# A78_Maxi2.net
KiCad netlist of a schematic drawn in EAGLE
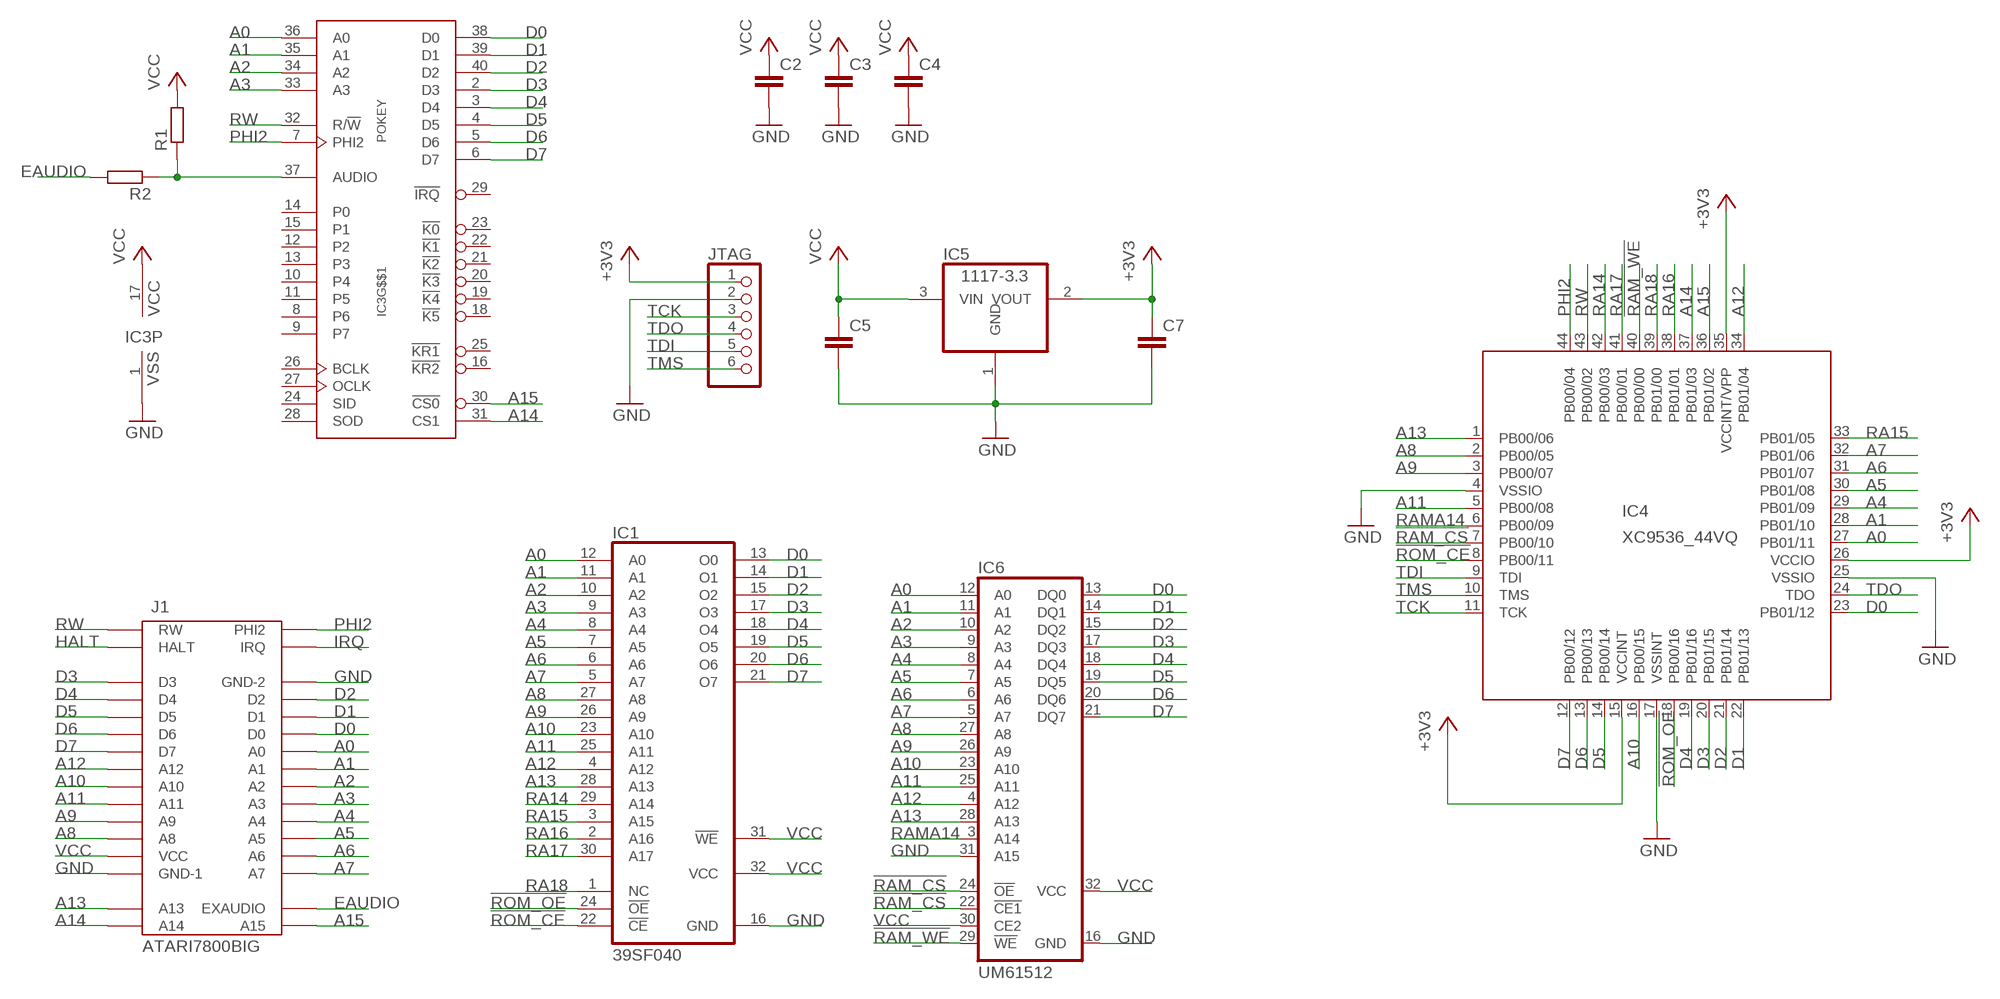
[diagram p0: schematic, sheet 1]

(export (version "E")
  (design (tool "Eeschema 10.0.6"))
  (components
    (comp (ref "C2")
      (value "C-EU025-025X050")
      (footprint "eagle-import:C025-025X050")
      (libsource (lib "eagle-import") (part "C-EU025-025X050"))
    )
    (comp (ref "C3")
      (value "C-EUC0805")
      (footprint "eagle-import:C0805")
      (libsource (lib "eagle-import") (part "C-EUC0805"))
    )
    (comp (ref "C4")
      (value "C-EUC0805")
      (footprint "eagle-import:C0805")
      (libsource (lib "eagle-import") (part "C-EUC0805"))
    )
    (comp (ref "C5")
      (value "C-EUC0805")
      (footprint "eagle-import:C0805")
      (libsource (lib "eagle-import") (part "C-EUC0805"))
    )
    (comp (ref "C7")
      (value "C-EUC0805")
      (footprint "eagle-import:C0805")
      (libsource (lib "eagle-import") (part "C-EUC0805"))
    )
    (comp (ref "IC1")
      (value "39SF040")
      (footprint "eagle-import:DIL32")
      (libsource (lib "eagle-import") (part "39SF020"))
    )
    (comp (ref "IC3")
      (value "POKEY")
      (footprint "eagle-import:DIL40")
      (libsource (lib "eagle-import") (part "POKEY"))
    )
    (comp (ref "IC4")
      (value "XC9536_44VQ")
      (footprint "eagle-import:SQFP-S-10X10-44")
      (fields (field (name "MPN") "XC9536-15VQG44C"))
      (libsource (lib "eagle-import") (part "XC9536_44VQ"))
    )
    (comp (ref "IC5")
      (value "1117-3.3")
      (footprint "eagle-import:SOT223")
      (fields (field (name "MPN") "REG1117"))
      (libsource (lib "eagle-import") (part "REG1117"))
    )
    (comp (ref "IC6")
      (value "UM61512")
      (footprint "eagle-import:DIL32-NARROW")
      (libsource (lib "eagle-import") (part "UM61512"))
    )
    (comp (ref "J1")
      (value "ATARI7800BIG")
      (footprint "eagle-import:ATARI-7800-BIG")
      (libsource (lib "eagle-import") (part "ATARI7800BIG"))
    )
    (comp (ref "JTAG")
      (value "PINHD-1X6")
      (footprint "eagle-import:1X06")
      (libsource (lib "eagle-import") (part "PINHD-1X6"))
    )
    (comp (ref "R1")
      (value "R-EU_R0805")
      (footprint "eagle-import:R0805")
      (libsource (lib "eagle-import") (part "R-EU_R0805"))
    )
    (comp (ref "R2")
      (value "R-EU_R0805")
      (footprint "eagle-import:R0805")
      (libsource (lib "eagle-import") (part "R-EU_R0805"))
    )
  )
  (nets
    (net (code "1") (name "+3V3") (class "Default")
      (node (ref "C7") (pin "1") (pinfunction "1_1") (pintype "passive"))
      (node (ref "IC4") (pin "15") (pinfunction "VCCINT_15") (pintype "power_in"))
      (node (ref "IC4") (pin "26") (pinfunction "VCCIO_26") (pintype "power_in"))
      (node (ref "IC4") (pin "35") (pinfunction "VCCINT/VPP_35") (pintype "input"))
      (node (ref "IC5") (pin "2") (pinfunction "VOUT_2") (pintype "output"))
      (node (ref "JTAG") (pin "1") (pinfunction "1_1") (pintype "passive"))
    )
    (net (code "2") (name "/A0") (class "Default")
      (node (ref "IC1") (pin "12") (pinfunction "A0_12") (pintype "input"))
      (node (ref "IC3") (pin "36") (pinfunction "A0_36") (pintype "input"))
      (node (ref "IC4") (pin "27") (pinfunction "PB01/11_27") (pintype "bidirectional"))
      (node (ref "IC6") (pin "12") (pinfunction "A0_12") (pintype "input"))
      (node (ref "J1") (pin "26") (pinfunction "A0_26") (pintype "passive"))
    )
    (net (code "3") (name "/A1") (class "Default")
      (node (ref "IC1") (pin "11") (pinfunction "A1_11") (pintype "input"))
      (node (ref "IC3") (pin "35") (pinfunction "A1_35") (pintype "input"))
      (node (ref "IC4") (pin "28") (pinfunction "PB01/10_28") (pintype "bidirectional"))
      (node (ref "IC6") (pin "11") (pinfunction "A1_11") (pintype "input"))
      (node (ref "J1") (pin "25") (pinfunction "A1_25") (pintype "passive"))
    )
    (net (code "4") (name "/A2") (class "Default")
      (node (ref "IC1") (pin "10") (pinfunction "A2_10") (pintype "input"))
      (node (ref "IC3") (pin "34") (pinfunction "A2_34") (pintype "input"))
      (node (ref "IC6") (pin "10") (pinfunction "A2_10") (pintype "input"))
      (node (ref "J1") (pin "24") (pinfunction "A2_24") (pintype "passive"))
    )
    (net (code "5") (name "/A3") (class "Default")
      (node (ref "IC1") (pin "9") (pinfunction "A3_9") (pintype "input"))
      (node (ref "IC3") (pin "33") (pinfunction "A3_33") (pintype "input"))
      (node (ref "IC6") (pin "9") (pinfunction "A3_9") (pintype "input"))
      (node (ref "J1") (pin "23") (pinfunction "A3_23") (pintype "passive"))
    )
    (net (code "6") (name "/A4") (class "Default")
      (node (ref "IC1") (pin "8") (pinfunction "A4_8") (pintype "input"))
      (node (ref "IC4") (pin "29") (pinfunction "PB01/09_29") (pintype "bidirectional"))
      (node (ref "IC6") (pin "8") (pinfunction "A4_8") (pintype "input"))
      (node (ref "J1") (pin "22") (pinfunction "A4_22") (pintype "passive"))
    )
    (net (code "7") (name "/A5") (class "Default")
      (node (ref "IC1") (pin "7") (pinfunction "A5_7") (pintype "input"))
      (node (ref "IC4") (pin "30") (pinfunction "PB01/08_30") (pintype "bidirectional"))
      (node (ref "IC6") (pin "7") (pinfunction "A5_7") (pintype "input"))
      (node (ref "J1") (pin "21") (pinfunction "A5_21") (pintype "passive"))
    )
    (net (code "8") (name "/A6") (class "Default")
      (node (ref "IC1") (pin "6") (pinfunction "A6_6") (pintype "input"))
      (node (ref "IC4") (pin "31") (pinfunction "PB01/07_31") (pintype "bidirectional"))
      (node (ref "IC6") (pin "6") (pinfunction "A6_6") (pintype "input"))
      (node (ref "J1") (pin "20") (pinfunction "A6_20") (pintype "passive"))
    )
    (net (code "9") (name "/A7") (class "Default")
      (node (ref "IC1") (pin "5") (pinfunction "A7_5") (pintype "input"))
      (node (ref "IC4") (pin "32") (pinfunction "PB01/06_32") (pintype "bidirectional"))
      (node (ref "IC6") (pin "5") (pinfunction "A7_5") (pintype "input"))
      (node (ref "J1") (pin "19") (pinfunction "A7_19") (pintype "passive"))
    )
    (net (code "10") (name "/A8") (class "Default")
      (node (ref "IC1") (pin "27") (pinfunction "A8_27") (pintype "input"))
      (node (ref "IC4") (pin "2") (pinfunction "PB00/05_2") (pintype "bidirectional"))
      (node (ref "IC6") (pin "27") (pinfunction "A8_27") (pintype "input"))
      (node (ref "J1") (pin "12") (pinfunction "A8_12") (pintype "passive"))
    )
    (net (code "11") (name "/A9") (class "Default")
      (node (ref "IC1") (pin "26") (pinfunction "A9_26") (pintype "input"))
      (node (ref "IC4") (pin "3") (pinfunction "PB00/07_3") (pintype "bidirectional"))
      (node (ref "IC6") (pin "26") (pinfunction "A9_26") (pintype "input"))
      (node (ref "J1") (pin "11") (pinfunction "A9_11") (pintype "passive"))
    )
    (net (code "12") (name "/A10") (class "Default")
      (node (ref "IC1") (pin "23") (pinfunction "A10_23") (pintype "input"))
      (node (ref "IC4") (pin "16") (pinfunction "PB00/15_16") (pintype "bidirectional"))
      (node (ref "IC6") (pin "23") (pinfunction "A10_23") (pintype "input"))
      (node (ref "J1") (pin "9") (pinfunction "A10_9") (pintype "passive"))
    )
    (net (code "13") (name "/A11") (class "Default")
      (node (ref "IC1") (pin "25") (pinfunction "A11_25") (pintype "input"))
      (node (ref "IC4") (pin "5") (pinfunction "PB00/08_5") (pintype "bidirectional"))
      (node (ref "IC6") (pin "25") (pinfunction "A11_25") (pintype "input"))
      (node (ref "J1") (pin "10") (pinfunction "A11_10") (pintype "passive"))
    )
    (net (code "14") (name "/A12") (class "Default")
      (node (ref "IC1") (pin "4") (pinfunction "A12_4") (pintype "input"))
      (node (ref "IC4") (pin "34") (pinfunction "PB01/04_34") (pintype "bidirectional"))
      (node (ref "IC6") (pin "4") (pinfunction "A12_4") (pintype "input"))
      (node (ref "J1") (pin "8") (pinfunction "A12_8") (pintype "passive"))
    )
    (net (code "15") (name "/A13") (class "Default")
      (node (ref "IC1") (pin "28") (pinfunction "A13_28") (pintype "input"))
      (node (ref "IC4") (pin "1") (pinfunction "PB00/06_1") (pintype "bidirectional"))
      (node (ref "IC6") (pin "28") (pinfunction "A13_28") (pintype "input"))
      (node (ref "J1") (pin "15") (pinfunction "A13_15") (pintype "passive"))
    )
    (net (code "16") (name "/A14") (class "Default")
      (node (ref "IC3") (pin "31") (pinfunction "CS1_31") (pintype "input"))
      (node (ref "IC4") (pin "37") (pinfunction "PB01/03_37") (pintype "bidirectional"))
      (node (ref "J1") (pin "16") (pinfunction "A14_16") (pintype "passive"))
    )
    (net (code "17") (name "/A15") (class "Default")
      (node (ref "IC3") (pin "30") (pinfunction "~{CS0}_30") (pintype "input"))
      (node (ref "IC4") (pin "36") (pinfunction "PB01/02_36") (pintype "bidirectional"))
      (node (ref "J1") (pin "17") (pinfunction "A15_17") (pintype "passive"))
    )
    (net (code "18") (name "/D0") (class "Default")
      (node (ref "IC1") (pin "13") (pinfunction "O0_13") (pintype "tri_state"))
      (node (ref "IC3") (pin "38") (pinfunction "D0_38") (pintype "output"))
      (node (ref "IC4") (pin "23") (pinfunction "PB01/12_23") (pintype "bidirectional"))
      (node (ref "IC6") (pin "13") (pinfunction "DQ0_13") (pintype "bidirectional"))
      (node (ref "J1") (pin "27") (pinfunction "D0_27") (pintype "passive"))
    )
    (net (code "19") (name "/D1") (class "Default")
      (node (ref "IC1") (pin "14") (pinfunction "O1_14") (pintype "tri_state"))
      (node (ref "IC3") (pin "39") (pinfunction "D1_39") (pintype "output"))
      (node (ref "IC4") (pin "22") (pinfunction "PB01/13_22") (pintype "bidirectional"))
      (node (ref "IC6") (pin "14") (pinfunction "DQ1_14") (pintype "bidirectional"))
      (node (ref "J1") (pin "28") (pinfunction "D1_28") (pintype "passive"))
    )
    (net (code "20") (name "/D2") (class "Default")
      (node (ref "IC1") (pin "15") (pinfunction "O2_15") (pintype "tri_state"))
      (node (ref "IC3") (pin "40") (pinfunction "D2_40") (pintype "output"))
      (node (ref "IC4") (pin "21") (pinfunction "PB01/14_21") (pintype "bidirectional"))
      (node (ref "IC6") (pin "15") (pinfunction "DQ2_15") (pintype "bidirectional"))
      (node (ref "J1") (pin "29") (pinfunction "D2_29") (pintype "passive"))
    )
    (net (code "21") (name "/D3") (class "Default")
      (node (ref "IC1") (pin "17") (pinfunction "O3_17") (pintype "tri_state"))
      (node (ref "IC3") (pin "2") (pinfunction "D3_2") (pintype "output"))
      (node (ref "IC4") (pin "20") (pinfunction "PB01/15_20") (pintype "bidirectional"))
      (node (ref "IC6") (pin "17") (pinfunction "DQ3_17") (pintype "bidirectional"))
      (node (ref "J1") (pin "3") (pinfunction "D3_3") (pintype "passive"))
    )
    (net (code "22") (name "/D4") (class "Default")
      (node (ref "IC1") (pin "18") (pinfunction "O4_18") (pintype "tri_state"))
      (node (ref "IC3") (pin "3") (pinfunction "D4_3") (pintype "output"))
      (node (ref "IC4") (pin "19") (pinfunction "PB01/16_19") (pintype "bidirectional"))
      (node (ref "IC6") (pin "18") (pinfunction "DQ4_18") (pintype "bidirectional"))
      (node (ref "J1") (pin "4") (pinfunction "D4_4") (pintype "passive"))
    )
    (net (code "23") (name "/D5") (class "Default")
      (node (ref "IC1") (pin "19") (pinfunction "O5_19") (pintype "tri_state"))
      (node (ref "IC3") (pin "4") (pinfunction "D5_4") (pintype "output"))
      (node (ref "IC4") (pin "14") (pinfunction "PB00/14_14") (pintype "bidirectional"))
      (node (ref "IC6") (pin "19") (pinfunction "DQ5_19") (pintype "bidirectional"))
      (node (ref "J1") (pin "5") (pinfunction "D5_5") (pintype "passive"))
    )
    (net (code "24") (name "/D6") (class "Default")
      (node (ref "IC1") (pin "20") (pinfunction "O6_20") (pintype "tri_state"))
      (node (ref "IC3") (pin "5") (pinfunction "D6_5") (pintype "output"))
      (node (ref "IC4") (pin "13") (pinfunction "PB00/13_13") (pintype "bidirectional"))
      (node (ref "IC6") (pin "20") (pinfunction "DQ6_20") (pintype "bidirectional"))
      (node (ref "J1") (pin "6") (pinfunction "D6_6") (pintype "passive"))
    )
    (net (code "25") (name "/D7") (class "Default")
      (node (ref "IC1") (pin "21") (pinfunction "O7_21") (pintype "tri_state"))
      (node (ref "IC3") (pin "6") (pinfunction "D7_6") (pintype "output"))
      (node (ref "IC4") (pin "12") (pinfunction "PB00/12_12") (pintype "bidirectional"))
      (node (ref "IC6") (pin "21") (pinfunction "DQ7_21") (pintype "bidirectional"))
      (node (ref "J1") (pin "7") (pinfunction "D7_7") (pintype "passive"))
    )
    (net (code "26") (name "/EAUDIO") (class "Default")
      (node (ref "J1") (pin "18") (pinfunction "EXAUDIO_18") (pintype "passive"))
      (node (ref "R2") (pin "2") (pinfunction "2_2") (pintype "passive"))
    )
    (net (code "27") (name "/HALT") (class "Default")
      (node (ref "J1") (pin "2") (pinfunction "HALT_2") (pintype "passive"))
    )
    (net (code "28") (name "/IRQ") (class "Default")
      (node (ref "J1") (pin "31") (pinfunction "IRQ_31") (pintype "passive"))
    )
    (net (code "29") (name "/PHI2") (class "Default")
      (node (ref "IC3") (pin "7") (pinfunction "PHI2_7") (pintype "input"))
      (node (ref "IC4") (pin "44") (pinfunction "PB00/04_44") (pintype "bidirectional"))
      (node (ref "J1") (pin "32") (pinfunction "PHI2_32") (pintype "passive"))
    )
    (net (code "30") (name "/RA14") (class "Default")
      (node (ref "IC1") (pin "29") (pinfunction "A14_29") (pintype "input"))
      (node (ref "IC4") (pin "42") (pinfunction "PB00/03_42") (pintype "bidirectional"))
    )
    (net (code "31") (name "/RA15") (class "Default")
      (node (ref "IC1") (pin "3") (pinfunction "A15_3") (pintype "input"))
      (node (ref "IC4") (pin "33") (pinfunction "PB01/05_33") (pintype "bidirectional"))
    )
    (net (code "32") (name "/RA16") (class "Default")
      (node (ref "IC1") (pin "2") (pinfunction "A16_2") (pintype "input"))
      (node (ref "IC4") (pin "38") (pinfunction "PB01/01_38") (pintype "bidirectional"))
    )
    (net (code "33") (name "/RA17") (class "Default")
      (node (ref "IC1") (pin "30") (pinfunction "A17_30") (pintype "input"))
      (node (ref "IC4") (pin "41") (pinfunction "PB00/01_41") (pintype "bidirectional"))
    )
    (net (code "34") (name "/RA18") (class "Default")
      (node (ref "IC1") (pin "1") (pinfunction "NC_1") (pintype "input"))
      (node (ref "IC4") (pin "39") (pinfunction "PB01/00_39") (pintype "bidirectional"))
    )
    (net (code "35") (name "/RAMA14") (class "Default")
      (node (ref "IC4") (pin "6") (pinfunction "PB00/09_6") (pintype "bidirectional"))
      (node (ref "IC6") (pin "3") (pinfunction "A14_3") (pintype "input"))
    )
    (net (code "36") (name "/RW") (class "Default")
      (node (ref "IC3") (pin "32") (pinfunction "R/~{W}_32") (pintype "input"))
      (node (ref "IC4") (pin "43") (pinfunction "PB00/02_43") (pintype "bidirectional"))
      (node (ref "J1") (pin "1") (pinfunction "RW_1") (pintype "passive"))
    )
    (net (code "37") (name "/TCK") (class "Default")
      (node (ref "IC4") (pin "11") (pinfunction "TCK_11") (pintype "input"))
      (node (ref "JTAG") (pin "3") (pinfunction "3_3") (pintype "passive"))
    )
    (net (code "38") (name "/TDI") (class "Default")
      (node (ref "IC4") (pin "9") (pinfunction "TDI_9") (pintype "input"))
      (node (ref "JTAG") (pin "5") (pinfunction "5_5") (pintype "passive"))
    )
    (net (code "39") (name "/TDO") (class "Default")
      (node (ref "IC4") (pin "24") (pinfunction "TDO_24") (pintype "output"))
      (node (ref "JTAG") (pin "4") (pinfunction "4_4") (pintype "passive"))
    )
    (net (code "40") (name "/TMS") (class "Default")
      (node (ref "IC4") (pin "10") (pinfunction "TMS_10") (pintype "input"))
      (node (ref "JTAG") (pin "6") (pinfunction "6_6") (pintype "passive"))
    )
    (net (code "41") (name "/~{RAM_CS}") (class "Default")
      (node (ref "IC4") (pin "7") (pinfunction "PB00/10_7") (pintype "bidirectional"))
      (node (ref "IC6") (pin "22") (pinfunction "~{CE1}_22") (pintype "input"))
      (node (ref "IC6") (pin "24") (pinfunction "~{OE}_24") (pintype "input"))
    )
    (net (code "42") (name "/~{RAM_WE}") (class "Default")
      (node (ref "IC4") (pin "40") (pinfunction "PB00/00_40") (pintype "bidirectional"))
      (node (ref "IC6") (pin "29") (pinfunction "~{WE}_29") (pintype "input"))
    )
    (net (code "43") (name "/~{ROM_CE}") (class "Default")
      (node (ref "IC1") (pin "22") (pinfunction "~{CE}_22") (pintype "input"))
      (node (ref "IC4") (pin "8") (pinfunction "PB00/11_8") (pintype "bidirectional"))
    )
    (net (code "44") (name "/~{ROM_OE}") (class "Default")
      (node (ref "IC1") (pin "24") (pinfunction "~{OE}_24") (pintype "input"))
      (node (ref "IC4") (pin "18") (pinfunction "PB00/16_18") (pintype "bidirectional"))
    )
    (net (code "45") (name "GND") (class "Default")
      (node (ref "C2") (pin "2") (pinfunction "2_2") (pintype "passive"))
      (node (ref "C3") (pin "2") (pinfunction "2_2") (pintype "passive"))
      (node (ref "C4") (pin "2") (pinfunction "2_2") (pintype "passive"))
      (node (ref "C5") (pin "2") (pinfunction "2_2") (pintype "passive"))
      (node (ref "C7") (pin "2") (pinfunction "2_2") (pintype "passive"))
      (node (ref "IC1") (pin "16") (pinfunction "GND_16") (pintype "power_in"))
      (node (ref "IC3") (pin "1") (pinfunction "VSS_1") (pintype "power_in"))
      (node (ref "IC4") (pin "17") (pinfunction "VSSINT_17") (pintype "power_in"))
      (node (ref "IC4") (pin "25") (pinfunction "VSSIO_25") (pintype "power_in"))
      (node (ref "IC4") (pin "4") (pinfunction "VSSIO_4") (pintype "power_in"))
      (node (ref "IC5") (pin "1") (pinfunction "GND_1") (pintype "power_in"))
      (node (ref "IC6") (pin "16") (pinfunction "GND_16") (pintype "power_in"))
      (node (ref "IC6") (pin "31") (pinfunction "A15_31") (pintype "input"))
      (node (ref "J1") (pin "14") (pinfunction "GND-1_14") (pintype "passive"))
      (node (ref "J1") (pin "30") (pinfunction "GND-2_30") (pintype "passive"))
      (node (ref "JTAG") (pin "2") (pinfunction "2_2") (pintype "passive"))
    )
    (net (code "46") (name "Net-(IC3A-AUDIO)") (class "Default")
      (node (ref "IC3") (pin "37") (pinfunction "AUDIO_37") (pintype "output"))
      (node (ref "R1") (pin "1") (pinfunction "1_1") (pintype "passive"))
      (node (ref "R2") (pin "1") (pinfunction "1_1") (pintype "passive"))
    )
    (net (code "47") (name "VCC") (class "Default")
      (node (ref "C2") (pin "1") (pinfunction "1_1") (pintype "passive"))
      (node (ref "C3") (pin "1") (pinfunction "1_1") (pintype "passive"))
      (node (ref "C4") (pin "1") (pinfunction "1_1") (pintype "passive"))
      (node (ref "C5") (pin "1") (pinfunction "1_1") (pintype "passive"))
      (node (ref "IC1") (pin "31") (pinfunction "~{WE}_31") (pintype "passive"))
      (node (ref "IC1") (pin "32") (pinfunction "VCC_32") (pintype "power_in"))
      (node (ref "IC3") (pin "17") (pinfunction "VCC_17") (pintype "power_in"))
      (node (ref "IC5") (pin "3") (pinfunction "VIN_3") (pintype "input"))
      (node (ref "IC6") (pin "30") (pinfunction "CE2_30") (pintype "input"))
      (node (ref "IC6") (pin "32") (pinfunction "VCC_32") (pintype "power_in"))
      (node (ref "J1") (pin "13") (pinfunction "VCC_13") (pintype "passive"))
      (node (ref "R1") (pin "2") (pinfunction "2_2") (pintype "passive"))
    )
    (net (code "48") (name "unconnected-(IC3A-BCLK-Pad26)") (class "Default")
      (node (ref "IC3") (pin "26") (pinfunction "BCLK_26") (pintype "bidirectional"))
    )
    (net (code "49") (name "unconnected-(IC3A-OCLK-Pad27)") (class "Default")
      (node (ref "IC3") (pin "27") (pinfunction "OCLK_27") (pintype "output"))
    )
    (net (code "50") (name "unconnected-(IC3A-P0-Pad14)") (class "Default")
      (node (ref "IC3") (pin "14") (pinfunction "P0_14") (pintype "input"))
    )
    (net (code "51") (name "unconnected-(IC3A-P1-Pad15)") (class "Default")
      (node (ref "IC3") (pin "15") (pinfunction "P1_15") (pintype "input"))
    )
    (net (code "52") (name "unconnected-(IC3A-P2-Pad12)") (class "Default")
      (node (ref "IC3") (pin "12") (pinfunction "P2_12") (pintype "input"))
    )
    (net (code "53") (name "unconnected-(IC3A-P3-Pad13)") (class "Default")
      (node (ref "IC3") (pin "13") (pinfunction "P3_13") (pintype "input"))
    )
    (net (code "54") (name "unconnected-(IC3A-P4-Pad10)") (class "Default")
      (node (ref "IC3") (pin "10") (pinfunction "P4_10") (pintype "input"))
    )
    (net (code "55") (name "unconnected-(IC3A-P5-Pad11)") (class "Default")
      (node (ref "IC3") (pin "11") (pinfunction "P5_11") (pintype "input"))
    )
    (net (code "56") (name "unconnected-(IC3A-P6-Pad8)") (class "Default")
      (node (ref "IC3") (pin "8") (pinfunction "P6_8") (pintype "input"))
    )
    (net (code "57") (name "unconnected-(IC3A-P7-Pad9)") (class "Default")
      (node (ref "IC3") (pin "9") (pinfunction "P7_9") (pintype "input"))
    )
    (net (code "58") (name "unconnected-(IC3A-SID-Pad24)") (class "Default")
      (node (ref "IC3") (pin "24") (pinfunction "SID_24") (pintype "input"))
    )
    (net (code "59") (name "unconnected-(IC3A-SOD-Pad28)") (class "Default")
      (node (ref "IC3") (pin "28") (pinfunction "SOD_28") (pintype "output"))
    )
    (net (code "60") (name "unconnected-(IC3A-~{IRQ}-Pad29)") (class "Default")
      (node (ref "IC3") (pin "29") (pinfunction "~{IRQ}_29") (pintype "output"))
    )
    (net (code "61") (name "unconnected-(IC3A-~{K0}-Pad23)") (class "Default")
      (node (ref "IC3") (pin "23") (pinfunction "~{K0}_23") (pintype "output"))
    )
    (net (code "62") (name "unconnected-(IC3A-~{K1}-Pad22)") (class "Default")
      (node (ref "IC3") (pin "22") (pinfunction "~{K1}_22") (pintype "output"))
    )
    (net (code "63") (name "unconnected-(IC3A-~{K2}-Pad21)") (class "Default")
      (node (ref "IC3") (pin "21") (pinfunction "~{K2}_21") (pintype "output"))
    )
    (net (code "64") (name "unconnected-(IC3A-~{K3}-Pad20)") (class "Default")
      (node (ref "IC3") (pin "20") (pinfunction "~{K3}_20") (pintype "output"))
    )
    (net (code "65") (name "unconnected-(IC3A-~{K4}-Pad19)") (class "Default")
      (node (ref "IC3") (pin "19") (pinfunction "~{K4}_19") (pintype "output"))
    )
    (net (code "66") (name "unconnected-(IC3A-~{K5}-Pad18)") (class "Default")
      (node (ref "IC3") (pin "18") (pinfunction "~{K5}_18") (pintype "output"))
    )
    (net (code "67") (name "unconnected-(IC3A-~{KR1}-Pad25)") (class "Default")
      (node (ref "IC3") (pin "25") (pinfunction "~{KR1}_25") (pintype "input"))
    )
    (net (code "68") (name "unconnected-(IC3A-~{KR2}-Pad16)") (class "Default")
      (node (ref "IC3") (pin "16") (pinfunction "~{KR2}_16") (pintype "input"))
    )
  )
)
